# MAX30100_Sensor.net
KiCad netlist of a schematic drawn in Altium Designer
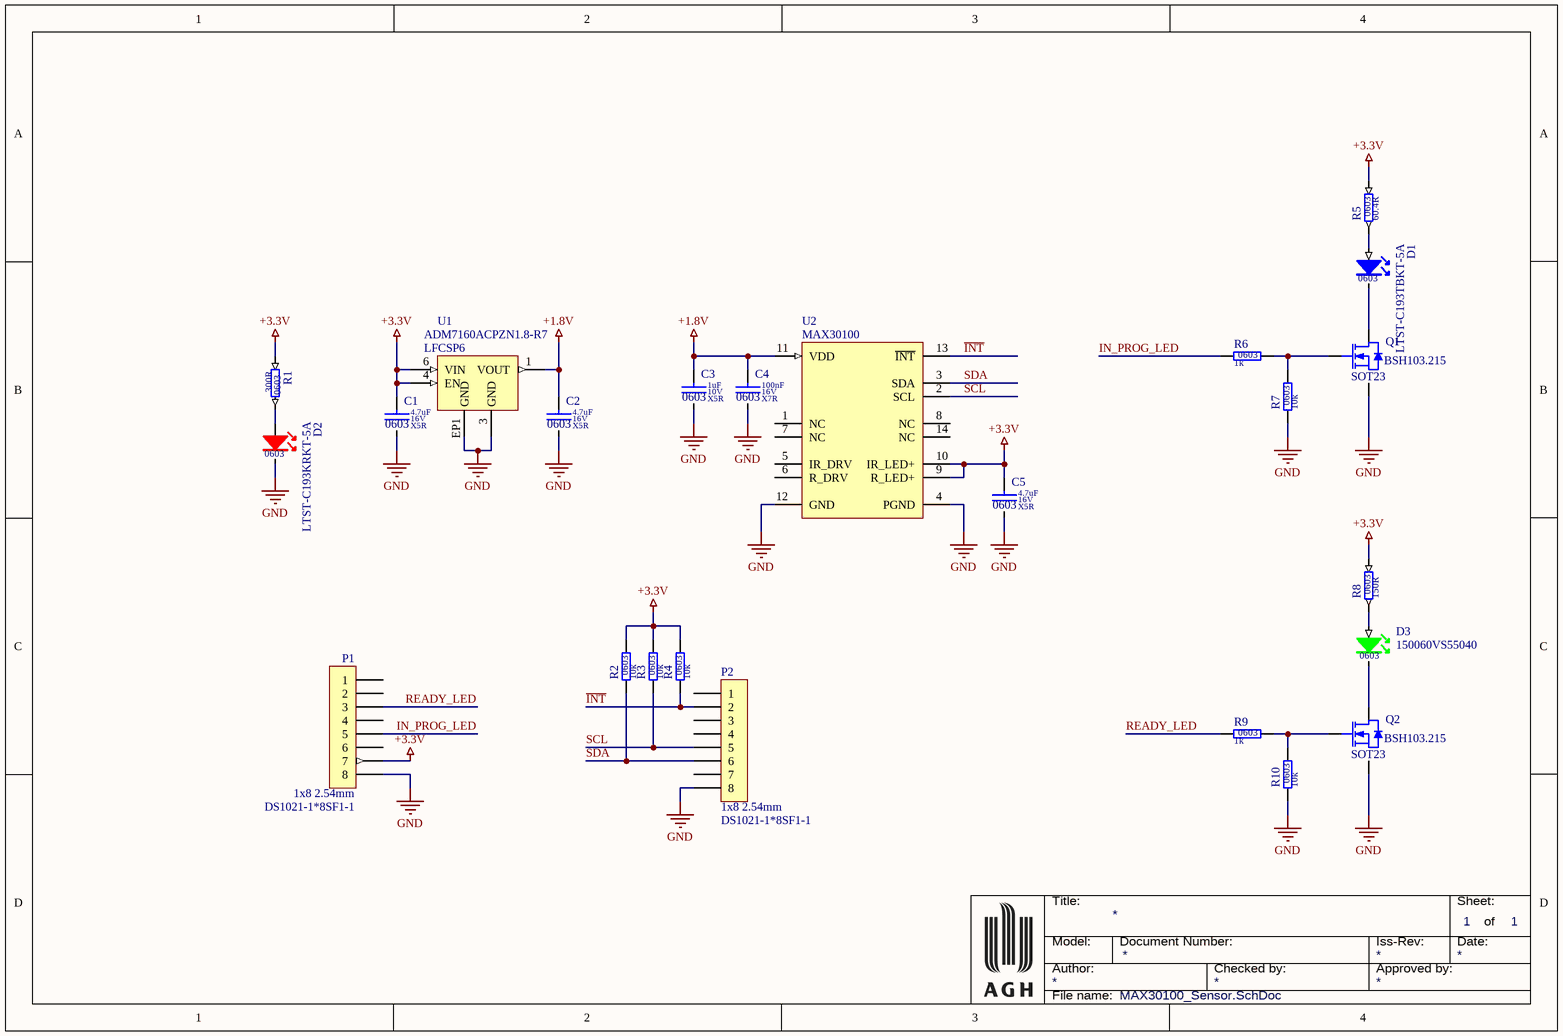
[diagram p0: MAX30100_Sensor.SchDoc]

(export (version "E")
  (design (tool "Eeschema 10.0.6"))
  (components
    (comp (ref "C1")
      (value "4.7uF")
      (footprint "C_0603_1608")
      (description "Capacitor")
      (fields
        (field (name "DIELECTRIC") "X5R")
        (field (name "VOLTAGE") "16V")
        (field (name "SCH_FOOTPRINT") "0603")
        (field (name "PART NUMBER") "C_4.7uF_16V_X5R_0603_10")
        (field (name "MANUFACTURER") "Murata")
      )
      (libsource (lib "Library") (part "C"))
    )
    (comp (ref "C2")
      (value "4.7uF")
      (footprint "C_0603_1608")
      (description "Capacitor")
      (fields
        (field (name "DIELECTRIC") "X5R")
        (field (name "VOLTAGE") "16V")
        (field (name "SCH_FOOTPRINT") "0603")
        (field (name "PART NUMBER") "C_4.7uF_16V_X5R_0603_10")
        (field (name "MANUFACTURER") "Murata")
      )
      (libsource (lib "Library") (part "C"))
    )
    (comp (ref "C3")
      (value "1uF")
      (footprint "C_0603_1608")
      (description "Capacitor")
      (fields
        (field (name "DIELECTRIC") "X5R")
        (field (name "VOLTAGE") "10V")
        (field (name "SCH_FOOTPRINT") "0603")
        (field (name "PART NUMBER") "C_1uF_10V_X5R_0603_10")
        (field (name "MANUFACTURER") "Murata")
      )
      (libsource (lib "Library") (part "C"))
    )
    (comp (ref "C4")
      (value "100nF")
      (footprint "C_0603_1608")
      (description "Capacitor")
      (fields
        (field (name "DIELECTRIC") "X7R")
        (field (name "VOLTAGE") "16V")
        (field (name "SCH_FOOTPRINT") "0603")
        (field (name "PART NUMBER") "C_100nF_16V_X7R_0603_10")
        (field (name "MANUFACTURER") "Kemet")
      )
      (libsource (lib "Library") (part "C"))
    )
    (comp (ref "C5")
      (value "4.7uF")
      (footprint "C_0603_1608")
      (description "Capacitor")
      (fields
        (field (name "DIELECTRIC") "X5R")
        (field (name "VOLTAGE") "16V")
        (field (name "SCH_FOOTPRINT") "0603")
        (field (name "PART NUMBER") "C_4.7uF_16V_X5R_0603_10")
        (field (name "MANUFACTURER") "Murata")
      )
      (libsource (lib "Library") (part "C"))
    )
    (comp (ref "D1")
      (value "LTST-C193TBKT-5A")
      (footprint "OL_0603_1608")
      (description "LED_BLUE")
      (fields
        (field (name "SCH_FOOTPRINT") "0603")
        (field (name "PART NUMBER") "OL_B_0603_LTST-C193TBKT-5A")
        (field (name "MANUFACTURER") "Lite-On")
      )
      (libsource (lib "Library") (part "OL_B"))
    )
    (comp (ref "D2")
      (value "LTST-C193KRKT-5A")
      (footprint "OL_0603_1608")
      (description "LED_RED")
      (fields
        (field (name "SCH_FOOTPRINT") "0603")
        (field (name "PART NUMBER") "OL_R_0603_LTST-C193KRKT-5A")
        (field (name "MANUFACTURER") "Lite-On")
      )
      (libsource (lib "Library") (part "OL_R"))
    )
    (comp (ref "D3")
      (value "150060VS55040")
      (footprint "OL_0603_1608")
      (description "LED GREEN")
      (fields
        (field (name "SCH_FOOTPRINT") "0603")
        (field (name "PART NUMBER") "OL_G_0603_150060VS55040")
        (field (name "MANUFACTURER") "Wurth")
      )
      (libsource (lib "Library") (part "OL_G"))
    )
    (comp (ref "P1")
      (value "DS1021-1*8SF1-1")
      (footprint "P_HEADER_1x8_2.54")
      (description "Pin Header")
      (fields
        (field (name "SCH_FOOTPRINT") "1x8 2.54mm")
        (field (name "PART NUMBER") "P_HEADER_1x8_2.54")
        (field (name "MANUFACTURER") "Connfly")
      )
      (libsource (lib "") (part "P_HEADER_1x8_1"))
    )
    (comp (ref "P2")
      (value "DS1021-1*8SF1-1")
      (footprint "P_HEADER_1x8_2.54")
      (description "Pin Header")
      (fields
        (field (name "SCH_FOOTPRINT") "1x8 2.54mm")
        (field (name "PART NUMBER") "P_HEADER_1x8_2.54")
        (field (name "MANUFACTURER") "Connfly")
      )
      (libsource (lib "Library") (part "P_HEADER_1x8"))
    )
    (comp (ref "Q1")
      (value "BSH103.215")
      (footprint "SOT23_TO236_SC59")
      (fields
        (field (name "SCH_FOOTPRINT") "SOT23")
        (field (name "PART NUMBER") "QN_BSH103")
        (field (name "VOLTAGE") "30V")
        (field (name "MANUFACTURER") "Nexperia")
      )
      (libsource (lib "Library") (part "QN_GSD"))
    )
    (comp (ref "Q2")
      (value "BSH103.215")
      (footprint "SOT23_TO236_SC59")
      (fields
        (field (name "SCH_FOOTPRINT") "SOT23")
        (field (name "PART NUMBER") "QN_BSH103")
        (field (name "VOLTAGE") "30V")
        (field (name "MANUFACTURER") "Nexperia")
      )
      (libsource (lib "Library") (part "QN_GSD"))
    )
    (comp (ref "R1")
      (value "300R")
      (footprint "R_0603_1608")
      (fields
        (field (name "SCH_FOOTPRINT") "0603")
        (field (name "PART NUMBER") "R_300R_0603_1")
        (field (name "VOLTAGE") "50V")
        (field (name "POWER") "100mW")
      )
      (libsource (lib "") (part "R_2"))
    )
    (comp (ref "R2")
      (value "10k")
      (footprint "R_0603_1608")
      (fields
        (field (name "SCH_FOOTPRINT") "0603")
        (field (name "PART NUMBER") "R_10k_0603_1")
        (field (name "VOLTAGE") "75V")
        (field (name "POWER") "100mW")
      )
      (libsource (lib "Library") (part "R"))
    )
    (comp (ref "R3")
      (value "10k")
      (footprint "R_0603_1608")
      (fields
        (field (name "SCH_FOOTPRINT") "0603")
        (field (name "PART NUMBER") "R_10k_0603_1")
        (field (name "VOLTAGE") "75V")
        (field (name "POWER") "100mW")
      )
      (libsource (lib "Library") (part "R"))
    )
    (comp (ref "R4")
      (value "10k")
      (footprint "R_0603_1608")
      (fields
        (field (name "SCH_FOOTPRINT") "0603")
        (field (name "PART NUMBER") "R_10k_0603_1")
        (field (name "VOLTAGE") "75V")
        (field (name "POWER") "100mW")
      )
      (libsource (lib "Library") (part "R"))
    )
    (comp (ref "R5")
      (value "60.4R")
      (footprint "R_0603_1608")
      (fields
        (field (name "SCH_FOOTPRINT") "0603")
        (field (name "PART NUMBER") "R_60.4R_0603_1")
        (field (name "VOLTAGE") "75V")
        (field (name "POWER") "100mW")
      )
      (libsource (lib "") (part "R_1"))
    )
    (comp (ref "R6")
      (value "1k")
      (footprint "R_0603_1608")
      (fields
        (field (name "SCH_FOOTPRINT") "0603")
        (field (name "PART NUMBER") "R_1k_0603_1")
        (field (name "VOLTAGE") "75V")
        (field (name "POWER") "100mW")
      )
      (libsource (lib "Library") (part "R"))
    )
    (comp (ref "R7")
      (value "10k")
      (footprint "R_0603_1608")
      (fields
        (field (name "SCH_FOOTPRINT") "0603")
        (field (name "PART NUMBER") "R_10k_0603_1")
        (field (name "VOLTAGE") "75V")
        (field (name "POWER") "100mW")
      )
      (libsource (lib "Library") (part "R"))
    )
    (comp (ref "R8")
      (value "150R")
      (footprint "R_0603_1608")
      (fields
        (field (name "SCH_FOOTPRINT") "0603")
        (field (name "PART NUMBER") "R_150R_0603_1")
        (field (name "VOLTAGE") "50V")
        (field (name "POWER") "100mW")
      )
      (libsource (lib "") (part "R_1"))
    )
    (comp (ref "R9")
      (value "1k")
      (footprint "R_0603_1608")
      (fields
        (field (name "SCH_FOOTPRINT") "0603")
        (field (name "PART NUMBER") "R_1k_0603_1")
        (field (name "VOLTAGE") "75V")
        (field (name "POWER") "100mW")
      )
      (libsource (lib "Library") (part "R"))
    )
    (comp (ref "R10")
      (value "10k")
      (footprint "R_0603_1608")
      (fields
        (field (name "SCH_FOOTPRINT") "0603")
        (field (name "PART NUMBER") "R_10k_0603_1")
        (field (name "VOLTAGE") "75V")
        (field (name "POWER") "100mW")
      )
      (libsource (lib "Library") (part "R"))
    )
    (comp (ref "U1")
      (value "ADM7160ACPZN1.8-R7")
      (footprint "LFCSP-6-3")
      (fields
        (field (name "SCH_FOOTPRINT") "LFCSP6")
        (field (name "PART NUMBER") "VL_ADM7160ACPZN1.8-R7")
        (field (name "VOLTAGE") "1.8V")
        (field (name "MANUFACTURER") "Analog Devices")
      )
      (libsource (lib "Library") (part "VL_ADM7160ACPZN"))
    )
    (comp (ref "U2")
      (value "MAX30100")
      (footprint "MAX30100")
      (fields (field (name "SCH_FOOTPRINT") "MAX30100") (field (name "PART NUMBER") "U_MAX30100"))
      (libsource (lib "Library") (part "U_MAX30100"))
    )
  )
  (nets
    (net (code "1") (name "+1.8V") (class "Default")
      (node (ref "C2") (pin "1") (pinfunction "1_1") (pintype "passive"))
      (node (ref "C3") (pin "1") (pinfunction "1_1") (pintype "passive"))
      (node (ref "C4") (pin "1") (pinfunction "1_1") (pintype "passive"))
      (node (ref "U1") (pin "1") (pinfunction "VOUT_1") (pintype "output"))
      (node (ref "U2") (pin "11") (pinfunction "VDD_11") (pintype "input"))
    )
    (net (code "2") (name "+3.3V") (class "Default")
      (node (ref "C1") (pin "1") (pinfunction "1_1") (pintype "passive"))
      (node (ref "C5") (pin "1") (pinfunction "1_1") (pintype "passive"))
      (node (ref "P1") (pin "7") (pinfunction "7_7") (pintype "output"))
      (node (ref "R1") (pin "1") (pinfunction "1_1") (pintype "input"))
      (node (ref "R2") (pin "2") (pinfunction "2_2") (pintype "passive"))
      (node (ref "R3") (pin "2") (pinfunction "2_2") (pintype "passive"))
      (node (ref "R4") (pin "2") (pinfunction "2_2") (pintype "passive"))
      (node (ref "R5") (pin "2") (pinfunction "2_2") (pintype "input"))
      (node (ref "R8") (pin "2") (pinfunction "2_2") (pintype "input"))
      (node (ref "U1") (pin "4") (pinfunction "EN_4") (pintype "input"))
      (node (ref "U1") (pin "6") (pinfunction "VIN_6") (pintype "input"))
      (node (ref "U2") (pin "10") (pinfunction "IR_LED+_10") (pintype "passive"))
      (node (ref "U2") (pin "9") (pinfunction "R_LED+_9") (pintype "passive"))
    )
    (net (code "3") (name "/IN_PROG_LED") (class "Default")
      (node (ref "P1") (pin "5") (pinfunction "5_5") (pintype "passive"))
      (node (ref "R6") (pin "1") (pinfunction "1_1") (pintype "passive"))
    )
    (net (code "4") (name "/READY_LED") (class "Default")
      (node (ref "P1") (pin "3") (pinfunction "3_3") (pintype "passive"))
      (node (ref "R9") (pin "1") (pinfunction "1_1") (pintype "passive"))
    )
    (net (code "5") (name "/SCL") (class "Default")
      (node (ref "P2") (pin "5") (pinfunction "5_5") (pintype "passive"))
      (node (ref "R3") (pin "1") (pinfunction "1_1") (pintype "passive"))
      (node (ref "U2") (pin "2") (pinfunction "SCL_2") (pintype "power_in"))
    )
    (net (code "6") (name "/SDA") (class "Default")
      (node (ref "P2") (pin "6") (pinfunction "6_6") (pintype "passive"))
      (node (ref "R2") (pin "1") (pinfunction "1_1") (pintype "passive"))
      (node (ref "U2") (pin "3") (pinfunction "SDA_3") (pintype "power_in"))
    )
    (net (code "7") (name "/~{INT}") (class "Default")
      (node (ref "P2") (pin "2") (pinfunction "2_2") (pintype "passive"))
      (node (ref "R4") (pin "1") (pinfunction "1_1") (pintype "passive"))
      (node (ref "U2") (pin "13") (pinfunction "~{INT}_13") (pintype "passive"))
    )
    (net (code "8") (name "GND") (class "Default")
      (node (ref "C1") (pin "2") (pinfunction "2_2") (pintype "passive"))
      (node (ref "C2") (pin "2") (pinfunction "2_2") (pintype "passive"))
      (node (ref "C3") (pin "2") (pinfunction "2_2") (pintype "passive"))
      (node (ref "C4") (pin "2") (pinfunction "2_2") (pintype "passive"))
      (node (ref "C5") (pin "2") (pinfunction "2_2") (pintype "passive"))
      (node (ref "D2") (pin "1") (pinfunction "K_1") (pintype "passive"))
      (node (ref "P1") (pin "8") (pinfunction "8_8") (pintype "passive"))
      (node (ref "P2") (pin "8") (pinfunction "8_8") (pintype "passive"))
      (node (ref "Q1") (pin "2") (pinfunction "S_2") (pintype "passive"))
      (node (ref "Q2") (pin "2") (pinfunction "S_2") (pintype "passive"))
      (node (ref "R10") (pin "1") (pinfunction "1_1") (pintype "passive"))
      (node (ref "R7") (pin "1") (pinfunction "1_1") (pintype "passive"))
      (node (ref "U1") (pin "3") (pinfunction "GND_3") (pintype "power_in"))
      (node (ref "U1") (pin "EP1") (pinfunction "GND_EP1") (pintype "power_in"))
      (node (ref "U2") (pin "12") (pinfunction "GND_12") (pintype "power_in"))
      (node (ref "U2") (pin "4") (pinfunction "PGND_4") (pintype "power_in"))
    )
    (net (code "9") (name "Net-(D1-A)") (class "Default")
      (node (ref "D1") (pin "2") (pinfunction "A_2") (pintype "input"))
      (node (ref "R5") (pin "1") (pinfunction "1_1") (pintype "output"))
    )
    (net (code "10") (name "Net-(D1-K)") (class "Default")
      (node (ref "D1") (pin "1") (pinfunction "K_1") (pintype "output"))
      (node (ref "Q1") (pin "3") (pinfunction "D_3") (pintype "passive"))
    )
    (net (code "11") (name "Net-(D2-A)") (class "Default")
      (node (ref "D2") (pin "2") (pinfunction "A_2") (pintype "passive"))
      (node (ref "R1") (pin "2") (pinfunction "2_2") (pintype "output"))
    )
    (net (code "12") (name "Net-(D3-A)") (class "Default")
      (node (ref "D3") (pin "2") (pinfunction "A_2") (pintype "input"))
      (node (ref "R8") (pin "1") (pinfunction "1_1") (pintype "output"))
    )
    (net (code "13") (name "Net-(D3-K)") (class "Default")
      (node (ref "D3") (pin "1") (pinfunction "K_1") (pintype "passive"))
      (node (ref "Q2") (pin "3") (pinfunction "D_3") (pintype "passive"))
    )
    (net (code "14") (name "Net-(Q1-G)") (class "Default")
      (node (ref "Q1") (pin "1") (pinfunction "G_1") (pintype "passive"))
      (node (ref "R6") (pin "2") (pinfunction "2_2") (pintype "passive"))
      (node (ref "R7") (pin "2") (pinfunction "2_2") (pintype "passive"))
    )
    (net (code "15") (name "Net-(Q2-G)") (class "Default")
      (node (ref "Q2") (pin "1") (pinfunction "G_1") (pintype "passive"))
      (node (ref "R10") (pin "2") (pinfunction "2_2") (pintype "passive"))
      (node (ref "R9") (pin "2") (pinfunction "2_2") (pintype "passive"))
    )
    (net (code "16") (name "unconnected-(P1-Pad1)") (class "Default")
      (node (ref "P1") (pin "1") (pinfunction "1_1") (pintype "passive"))
    )
    (net (code "17") (name "unconnected-(P1-Pad2)") (class "Default")
      (node (ref "P1") (pin "2") (pinfunction "2_2") (pintype "passive"))
    )
    (net (code "18") (name "unconnected-(P1-Pad4)") (class "Default")
      (node (ref "P1") (pin "4") (pinfunction "4_4") (pintype "passive"))
    )
    (net (code "19") (name "unconnected-(P1-Pad6)") (class "Default")
      (node (ref "P1") (pin "6") (pinfunction "6_6") (pintype "passive"))
    )
    (net (code "20") (name "unconnected-(P2-Pad1)") (class "Default")
      (node (ref "P2") (pin "1") (pinfunction "1_1") (pintype "passive"))
    )
    (net (code "21") (name "unconnected-(P2-Pad3)") (class "Default")
      (node (ref "P2") (pin "3") (pinfunction "3_3") (pintype "passive"))
    )
    (net (code "22") (name "unconnected-(P2-Pad4)") (class "Default")
      (node (ref "P2") (pin "4") (pinfunction "4_4") (pintype "passive"))
    )
    (net (code "23") (name "unconnected-(P2-Pad7)") (class "Default")
      (node (ref "P2") (pin "7") (pinfunction "7_7") (pintype "passive"))
    )
    (net (code "24") (name "unconnected-(U1-NC-Pad2)") (class "Default")
      (node (ref "U1") (pin "2") (pinfunction "NC_2") (pintype "passive"))
    )
    (net (code "25") (name "unconnected-(U1-NC-Pad5)") (class "Default")
      (node (ref "U1") (pin "5") (pinfunction "NC_5") (pintype "passive"))
    )
    (net (code "26") (name "unconnected-(U2-IR_DRV-Pad5)") (class "Default")
      (node (ref "U2") (pin "5") (pinfunction "IR_DRV_5") (pintype "power_in"))
    )
    (net (code "27") (name "unconnected-(U2-NC-Pad1)") (class "Default")
      (node (ref "U2") (pin "1") (pinfunction "NC_1") (pintype "passive"))
    )
    (net (code "28") (name "unconnected-(U2-NC-Pad7)") (class "Default")
      (node (ref "U2") (pin "7") (pinfunction "NC_7") (pintype "passive"))
    )
    (net (code "29") (name "unconnected-(U2-NC-Pad8)") (class "Default")
      (node (ref "U2") (pin "8") (pinfunction "NC_8") (pintype "passive"))
    )
    (net (code "30") (name "unconnected-(U2-NC-Pad14)") (class "Default")
      (node (ref "U2") (pin "14") (pinfunction "NC_14") (pintype "passive"))
    )
    (net (code "31") (name "unconnected-(U2-R_DRV-Pad6)") (class "Default")
      (node (ref "U2") (pin "6") (pinfunction "R_DRV_6") (pintype "power_in"))
    )
  )
)
